# Solenoid_11.net
KiCad netlist of a schematic drawn in EAGLE
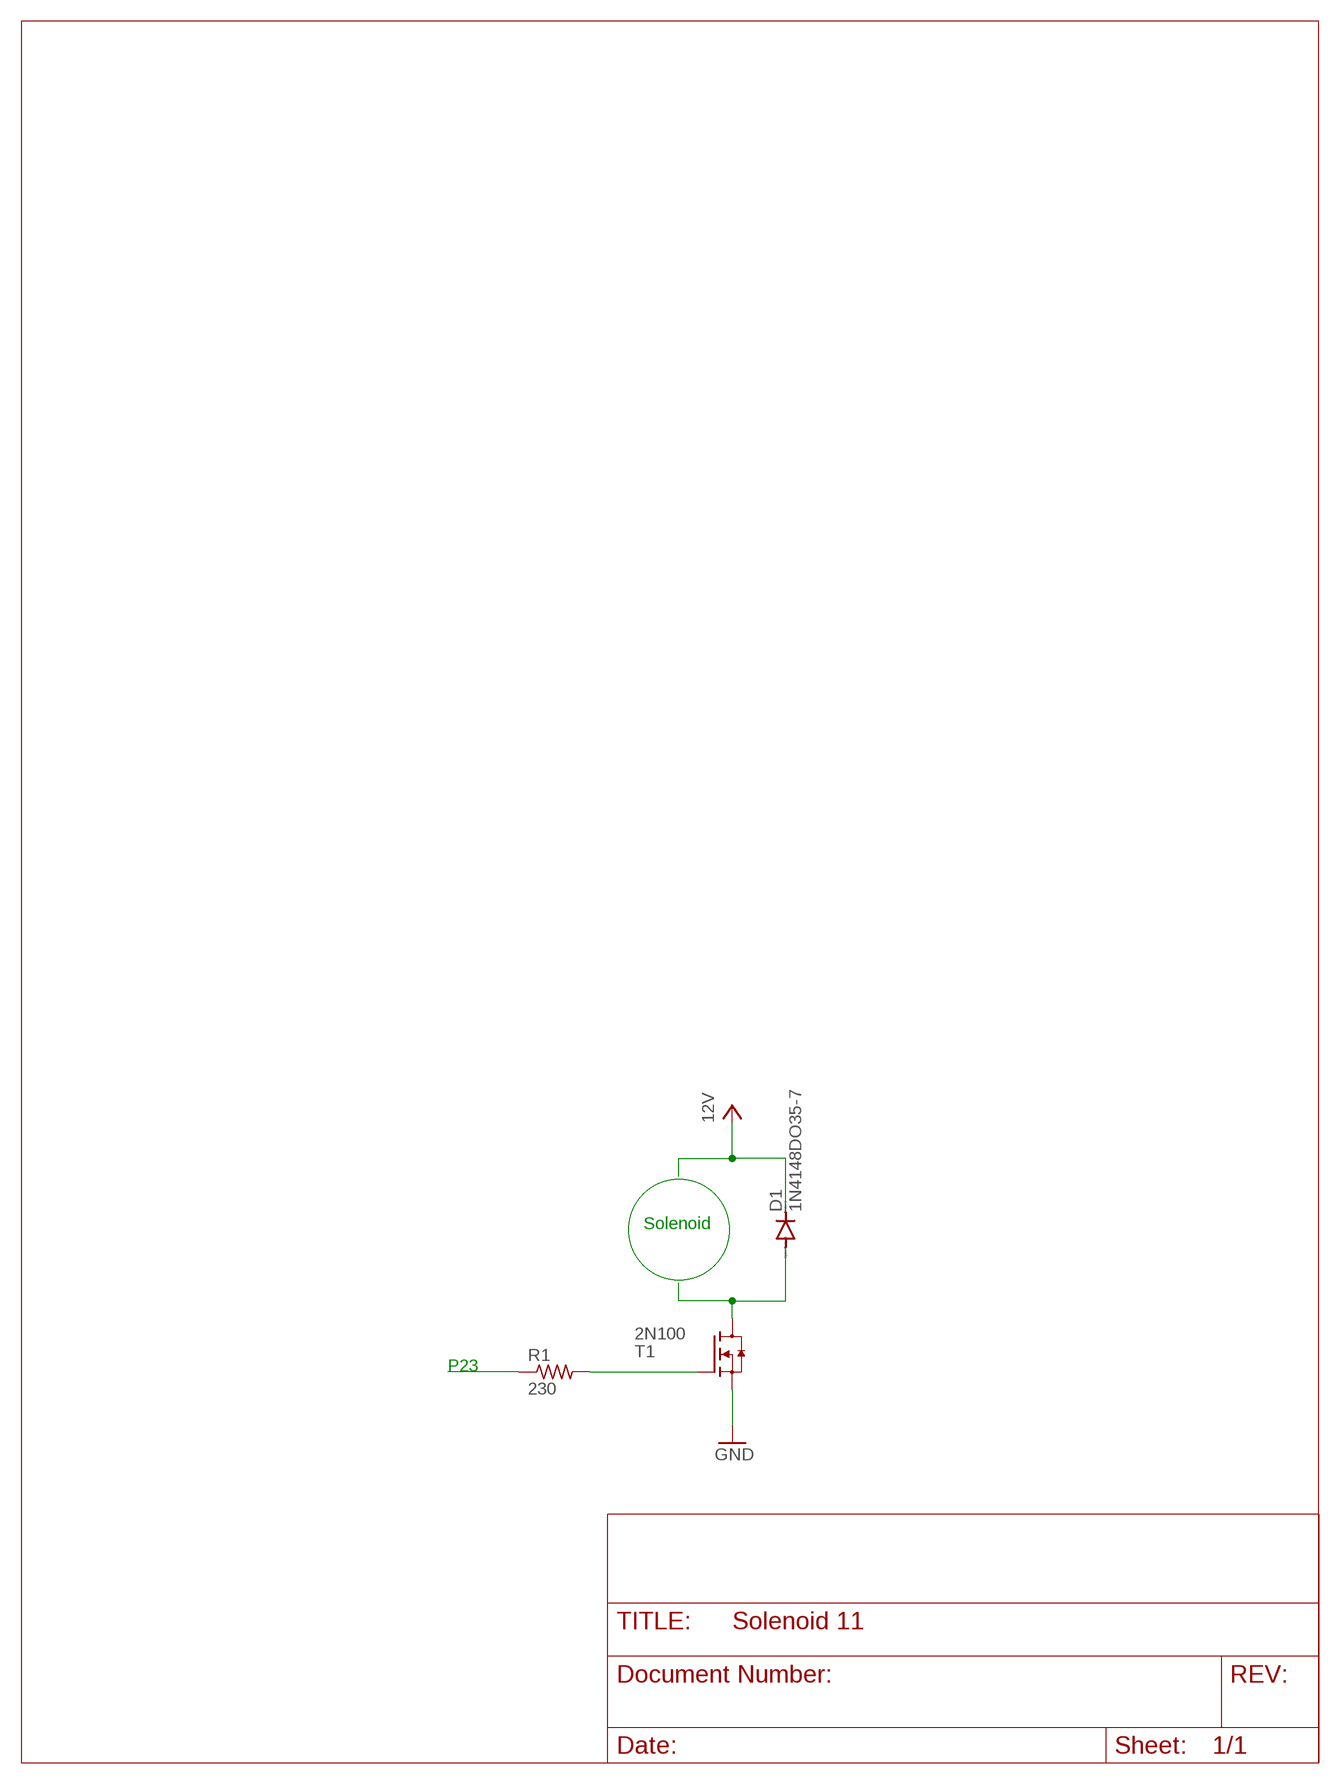
[diagram p0: schematic, sheet 1]

(export (version "E")
  (design (tool "Eeschema 10.0.6"))
  (components
    (comp (ref "D1")
      (value "1N4148DO35-7")
      (footprint "eagle-import:DO35-7")
      (libsource (lib "eagle-import") (part "1N4148DO35-7"))
    )
    (comp (ref "R1")
      (value "230")
      (footprint "eagle-import:0204_7")
      (libsource (lib "eagle-import") (part "R-US_0204/7"))
    )
    (comp (ref "T1")
      (value "2N100")
      (footprint "eagle-import:PG-TO263-7-3")
      (libsource (lib "eagle-import") (part "IPB180N06S4-H1"))
    )
  )
  (nets
    (net (code "1") (name "12V") (class "Default")
      (node (ref "D1") (pin "C") (pinfunction "C_C") (pintype "passive"))
    )
    (net (code "2") (name "GND") (class "Default")
      (node (ref "T1") (pin "2") (pinfunction "S_2") (pintype "passive"))
      (node (ref "T1") (pin "3") (pinfunction "S_3") (pintype "passive"))
      (node (ref "T1") (pin "5") (pinfunction "S_5") (pintype "passive"))
      (node (ref "T1") (pin "6") (pinfunction "S_6") (pintype "passive"))
      (node (ref "T1") (pin "7") (pinfunction "S_7") (pintype "passive"))
    )
    (net (code "3") (name "Net-(T1-D)") (class "Default")
      (node (ref "D1") (pin "A") (pinfunction "A_A") (pintype "passive"))
      (node (ref "T1") (pin "8") (pinfunction "D_8") (pintype "passive"))
    )
    (net (code "4") (name "Net-(T1-G)") (class "Default")
      (node (ref "R1") (pin "2") (pinfunction "2_2") (pintype "passive"))
      (node (ref "T1") (pin "1") (pinfunction "G_1") (pintype "passive"))
    )
    (net (code "5") (name "unconnected-(R1-Pad1)") (class "Default")
      (node (ref "R1") (pin "1") (pinfunction "1_1") (pintype "passive"))
    )
  )
)
